# WheelLED_Light_Sch.net
KiCad netlist of a schematic drawn in Altium Designer
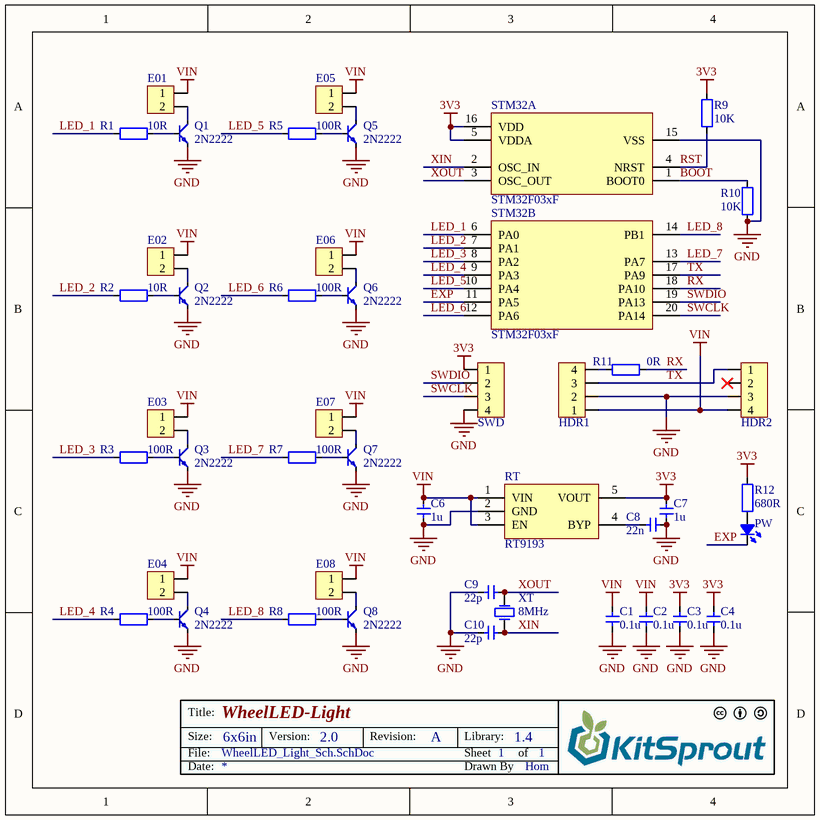
[diagram p0: WheelLED_Light_Sch.SchDoc]

(export (version "E")
  (design (tool "Eeschema 10.0.6"))
  (components
    (comp (ref "C1")
      (value "0.1u")
      (footprint "PCB_PassiveCap:CAP_0603")
      (description "Capacitor")
      (fields (field (name "Comment") "Cap_0603"))
      (libsource (lib "SCH_Passive") (part "Cap_0603"))
    )
    (comp (ref "C2")
      (value "0.1u")
      (footprint "PCB_PassiveCap:CAP_0603")
      (description "Capacitor")
      (fields (field (name "Comment") "Cap_0603"))
      (libsource (lib "SCH_Passive") (part "Cap_0603"))
    )
    (comp (ref "C3")
      (value "0.1u")
      (footprint "PCB_PassiveCap:CAP_0603")
      (description "Capacitor")
      (fields (field (name "Comment") "Cap_0603"))
      (libsource (lib "SCH_Passive") (part "Cap_0603"))
    )
    (comp (ref "C4")
      (value "0.1u")
      (footprint "PCB_PassiveCap:CAP_0603")
      (description "Capacitor")
      (fields (field (name "Comment") "Cap_0603"))
      (libsource (lib "SCH_Passive") (part "Cap_0603"))
    )
    (comp (ref "C6")
      (value "1u")
      (footprint "PCB_PassiveCap:CAP_0603")
      (description "Capacitor")
      (fields (field (name "Comment") "Cap_0603"))
      (libsource (lib "SCH_Passive") (part "Cap_0603"))
    )
    (comp (ref "C7")
      (value "1u")
      (footprint "PCB_PassiveCap:CAP_0603")
      (description "Capacitor")
      (fields (field (name "Comment") "Cap_0603"))
      (libsource (lib "SCH_Passive") (part "Cap_0603"))
    )
    (comp (ref "C8")
      (value "22n")
      (footprint "PCB_PassiveCap:CAP_0603")
      (description "Capacitor")
      (fields (field (name "Comment") "Cap_0603"))
      (libsource (lib "SCH_Passive") (part "Cap_0603"))
    )
    (comp (ref "C9")
      (value "22p")
      (footprint "PCB_PassiveCap:CAP_0603")
      (description "Capacitor")
      (fields (field (name "Comment") "Cap_0603"))
      (libsource (lib "SCH_Passive") (part "Cap_0603"))
    )
    (comp (ref "C10")
      (value "22p")
      (footprint "PCB_PassiveCap:CAP_0603")
      (description "Capacitor")
      (fields (field (name "Comment") "Cap_0603"))
      (libsource (lib "SCH_Passive") (part "Cap_0603"))
    )
    (comp (ref "E01")
      (value "HDR1x2_2.54")
      (footprint "PCB_ConnectorHDR:HDR1X2_2.54_180H")
      (description "Header")
      (libsource (lib "SCH_ConnectorHDR") (part "HDR1x2_2.54T"))
    )
    (comp (ref "E02")
      (value "HDR1x2_2.54")
      (footprint "PCB_ConnectorHDR:HDR1X2_2.54_180H")
      (description "Header")
      (libsource (lib "SCH_ConnectorHDR") (part "HDR1x2_2.54T"))
    )
    (comp (ref "E03")
      (value "HDR1x2_2.54")
      (footprint "PCB_ConnectorHDR:HDR1X2_2.54_180H")
      (description "Header")
      (libsource (lib "SCH_ConnectorHDR") (part "HDR1x2_2.54T"))
    )
    (comp (ref "E04")
      (value "HDR1x2_2.54")
      (footprint "PCB_ConnectorHDR:HDR1X2_2.54_180H")
      (description "Header")
      (libsource (lib "SCH_ConnectorHDR") (part "HDR1x2_2.54T"))
    )
    (comp (ref "E05")
      (value "HDR1x2_2.54")
      (footprint "PCB_ConnectorHDR:HDR1X2_2.54_180H")
      (description "Header")
      (libsource (lib "SCH_ConnectorHDR") (part "HDR1x2_2.54T"))
    )
    (comp (ref "E06")
      (value "HDR1x2_2.54")
      (footprint "PCB_ConnectorHDR:HDR1X2_2.54_180H")
      (description "Header")
      (libsource (lib "SCH_ConnectorHDR") (part "HDR1x2_2.54T"))
    )
    (comp (ref "E07")
      (value "HDR1x2_2.54")
      (footprint "PCB_ConnectorHDR:HDR1X2_2.54_180H")
      (description "Header")
      (libsource (lib "SCH_ConnectorHDR") (part "HDR1x2_2.54T"))
    )
    (comp (ref "E08")
      (value "HDR1x2_2.54")
      (footprint "PCB_ConnectorHDR:HDR1X2_2.54_180H")
      (description "Header")
      (libsource (lib "SCH_ConnectorHDR") (part "HDR1x2_2.54T"))
    )
    (comp (ref "HDR1")
      (value "HDR1x4_2.54")
      (footprint "PCB_ConnectorHDR:HDR1X4_2.54_90F")
      (description "Header")
      (libsource (lib "SCH_ConnectorHDR") (part "HDR1x4_2.54"))
    )
    (comp (ref "HDR2")
      (value "HDR1x4_2.54")
      (footprint "PCB_ConnectorHDR:HDR1X4_2.54_180H")
      (description "Header")
      (libsource (lib "") (part "HDR1x4_2.54_1"))
    )
    (comp (ref "PW")
      (value "LED_0805")
      (footprint "PCB_ActiveLED:LED_0805_GREEN")
      (description "LED")
      (libsource (lib "SCH_Active") (part "LED_0805"))
    )
    (comp (ref "Q1")
      (value "2N2222")
      (footprint "PCB_IntegratedCircuit:SOT23-3")
      (description "Transistor")
      (fields (field (name "Comment") "BJT_NPN"))
      (libsource (lib "SCH_Active") (part "BJT_NPN"))
    )
    (comp (ref "Q2")
      (value "2N2222")
      (footprint "PCB_IntegratedCircuit:SOT23-3")
      (description "Transistor")
      (fields (field (name "Comment") "BJT_NPN"))
      (libsource (lib "SCH_Active") (part "BJT_NPN"))
    )
    (comp (ref "Q3")
      (value "2N2222")
      (footprint "PCB_IntegratedCircuit:SOT23-3")
      (description "Transistor")
      (fields (field (name "Comment") "BJT_NPN"))
      (libsource (lib "SCH_Active") (part "BJT_NPN"))
    )
    (comp (ref "Q4")
      (value "2N2222")
      (footprint "PCB_IntegratedCircuit:SOT23-3")
      (description "Transistor")
      (fields (field (name "Comment") "BJT_NPN"))
      (libsource (lib "SCH_Active") (part "BJT_NPN"))
    )
    (comp (ref "Q5")
      (value "2N2222")
      (footprint "PCB_IntegratedCircuit:SOT23-3")
      (description "Transistor")
      (fields (field (name "Comment") "BJT_NPN"))
      (libsource (lib "SCH_Active") (part "BJT_NPN"))
    )
    (comp (ref "Q6")
      (value "2N2222")
      (footprint "PCB_IntegratedCircuit:SOT23-3")
      (description "Transistor")
      (fields (field (name "Comment") "BJT_NPN"))
      (libsource (lib "SCH_Active") (part "BJT_NPN"))
    )
    (comp (ref "Q7")
      (value "2N2222")
      (footprint "PCB_IntegratedCircuit:SOT23-3")
      (description "Transistor")
      (fields (field (name "Comment") "BJT_NPN"))
      (libsource (lib "SCH_Active") (part "BJT_NPN"))
    )
    (comp (ref "Q8")
      (value "2N2222")
      (footprint "PCB_IntegratedCircuit:SOT23-3")
      (description "Transistor")
      (fields (field (name "Comment") "BJT_NPN"))
      (libsource (lib "SCH_Active") (part "BJT_NPN"))
    )
    (comp (ref "R1")
      (value "10R")
      (footprint "PCB_PassiveRes:RES_0603")
      (description "Resistor")
      (fields (field (name "Comment") "Res_0603"))
      (libsource (lib "SCH_Passive") (part "Res_0603"))
    )
    (comp (ref "R2")
      (value "10R")
      (footprint "PCB_PassiveRes:RES_0603")
      (description "Resistor")
      (fields (field (name "Comment") "Res_0603"))
      (libsource (lib "SCH_Passive") (part "Res_0603"))
    )
    (comp (ref "R3")
      (value "100R")
      (footprint "PCB_PassiveRes:RES_0603")
      (description "Resistor")
      (fields (field (name "Comment") "Res_0603"))
      (libsource (lib "SCH_Passive") (part "Res_0603"))
    )
    (comp (ref "R4")
      (value "100R")
      (footprint "PCB_PassiveRes:RES_0603")
      (description "Resistor")
      (fields (field (name "Comment") "Res_0603"))
      (libsource (lib "SCH_Passive") (part "Res_0603"))
    )
    (comp (ref "R5")
      (value "100R")
      (footprint "PCB_PassiveRes:RES_0603")
      (description "Resistor")
      (fields (field (name "Comment") "Res_0603"))
      (libsource (lib "SCH_Passive") (part "Res_0603"))
    )
    (comp (ref "R6")
      (value "100R")
      (footprint "PCB_PassiveRes:RES_0603")
      (description "Resistor")
      (fields (field (name "Comment") "Res_0603"))
      (libsource (lib "SCH_Passive") (part "Res_0603"))
    )
    (comp (ref "R7")
      (value "100R")
      (footprint "PCB_PassiveRes:RES_0603")
      (description "Resistor")
      (fields (field (name "Comment") "Res_0603"))
      (libsource (lib "SCH_Passive") (part "Res_0603"))
    )
    (comp (ref "R8")
      (value "100R")
      (footprint "PCB_PassiveRes:RES_0603")
      (description "Resistor")
      (fields (field (name "Comment") "Res_0603"))
      (libsource (lib "SCH_Passive") (part "Res_0603"))
    )
    (comp (ref "R9")
      (value "10K")
      (footprint "PCB_PassiveRes:RES_0603")
      (description "Resistor")
      (fields (field (name "Comment") "Res_0603"))
      (libsource (lib "") (part "Res_0603_1"))
    )
    (comp (ref "R10")
      (value "10K")
      (footprint "PCB_PassiveRes:RES_0603")
      (description "Resistor")
      (fields (field (name "Comment") "Res_0603"))
      (libsource (lib "") (part "Res_0603_1"))
    )
    (comp (ref "R11")
      (value "0R")
      (footprint "PCB_PassiveRes:RES_0603")
      (description "Resistor")
      (fields (field (name "Comment") "Res_0603"))
      (libsource (lib "SCH_Passive") (part "Res_0603"))
    )
    (comp (ref "R12")
      (value "680R")
      (footprint "PCB_PassiveRes:RES_0805")
      (description "Resistor")
      (fields (field (name "Comment") "Res_0805"))
      (libsource (lib "SCH_Passive") (part "Res_0805"))
    )
    (comp (ref "RT")
      (value "RT9193")
      (footprint "PCB_IntegratedCircuit:SOT23-5")
      (description "Power")
      (libsource (lib "SCH_IntegratedCircuit") (part "RT9193"))
    )
    (comp (ref "STM32")
      (value "STM32F03xF")
      (footprint "PCB_IntegratedCircuit:TSSOP_E170_P0.65_20")
      (description "MCU")
      (libsource (lib "SCH_IntegratedCircuit") (part "STM32F03xF"))
    )
    (comp (ref "SWD")
      (value "HDR1x4_1.27")
      (footprint "PCB_ConnectorHDR:HDR1X4_1.27_180")
      (description "Header")
      (libsource (lib "SCH_ConnectorHDR") (part "HDR1x4_1.27"))
    )
    (comp (ref "XT")
      (value "8MHz")
      (footprint "PCB_Oscillator:XT_3225_2")
      (description "Crystal Oscillator")
      (fields (field (name "Comment") "XTAL_3225_2P"))
      (libsource (lib "SCH_Oscillator") (part "XTAL_3225_2P"))
    )
  )
  (nets
    (net (code "1") (name "/BOOT") (class "Default")
      (node (ref "R10") (pin "1") (pinfunction "1_1") (pintype "passive"))
      (node (ref "STM32") (pin "1") (pinfunction "BOOT0_1") (pintype "passive"))
    )
    (net (code "2") (name "/EXP") (class "Default")
      (node (ref "PW") (pin "2") (pinfunction "K_2") (pintype "passive"))
      (node (ref "STM32") (pin "11") (pinfunction "PA5_11") (pintype "passive"))
    )
    (net (code "3") (name "/LED_1") (class "Default")
      (node (ref "R1") (pin "1") (pinfunction "1_1") (pintype "passive"))
      (node (ref "STM32") (pin "6") (pinfunction "PA0_6") (pintype "passive"))
    )
    (net (code "4") (name "/LED_2") (class "Default")
      (node (ref "R2") (pin "1") (pinfunction "1_1") (pintype "passive"))
      (node (ref "STM32") (pin "7") (pinfunction "PA1_7") (pintype "passive"))
    )
    (net (code "5") (name "/LED_3") (class "Default")
      (node (ref "R3") (pin "1") (pinfunction "1_1") (pintype "passive"))
      (node (ref "STM32") (pin "8") (pinfunction "PA2_8") (pintype "passive"))
    )
    (net (code "6") (name "/LED_4") (class "Default")
      (node (ref "R4") (pin "1") (pinfunction "1_1") (pintype "passive"))
      (node (ref "STM32") (pin "9") (pinfunction "PA3_9") (pintype "passive"))
    )
    (net (code "7") (name "/LED_5") (class "Default")
      (node (ref "R5") (pin "1") (pinfunction "1_1") (pintype "passive"))
      (node (ref "STM32") (pin "10") (pinfunction "PA4_10") (pintype "passive"))
    )
    (net (code "8") (name "/LED_6") (class "Default")
      (node (ref "R6") (pin "1") (pinfunction "1_1") (pintype "passive"))
      (node (ref "STM32") (pin "12") (pinfunction "PA6_12") (pintype "passive"))
    )
    (net (code "9") (name "/LED_7") (class "Default")
      (node (ref "R7") (pin "1") (pinfunction "1_1") (pintype "passive"))
      (node (ref "STM32") (pin "13") (pinfunction "PA7_13") (pintype "passive"))
    )
    (net (code "10") (name "/LED_8") (class "Default")
      (node (ref "R8") (pin "1") (pinfunction "1_1") (pintype "passive"))
      (node (ref "STM32") (pin "14") (pinfunction "PB1_14") (pintype "passive"))
    )
    (net (code "11") (name "/RST") (class "Default")
      (node (ref "R9") (pin "2") (pinfunction "2_2") (pintype "passive"))
      (node (ref "STM32") (pin "4") (pinfunction "NRST_4") (pintype "passive"))
    )
    (net (code "12") (name "/RX") (class "Default")
      (node (ref "R11") (pin "2") (pinfunction "2_2") (pintype "passive"))
      (node (ref "STM32") (pin "18") (pinfunction "PA10_18") (pintype "passive"))
    )
    (net (code "13") (name "/SWCLK") (class "Default")
      (node (ref "STM32") (pin "20") (pinfunction "PA14_20") (pintype "passive"))
      (node (ref "SWD") (pin "3") (pinfunction "3_3") (pintype "passive"))
    )
    (net (code "14") (name "/SWDIO") (class "Default")
      (node (ref "STM32") (pin "19") (pinfunction "PA13_19") (pintype "passive"))
      (node (ref "SWD") (pin "2") (pinfunction "2_2") (pintype "passive"))
    )
    (net (code "15") (name "/TX") (class "Default")
      (node (ref "HDR1") (pin "3") (pinfunction "3_3") (pintype "passive"))
      (node (ref "HDR2") (pin "1") (pinfunction "1_1") (pintype "passive"))
      (node (ref "STM32") (pin "17") (pinfunction "PA9_17") (pintype "passive"))
    )
    (net (code "16") (name "/XIN") (class "Default")
      (node (ref "C10") (pin "1") (pinfunction "1_1") (pintype "passive"))
      (node (ref "STM32") (pin "2") (pinfunction "OSC_IN_2") (pintype "passive"))
      (node (ref "XT") (pin "1") (pinfunction "OSC1_1") (pintype "passive"))
    )
    (net (code "17") (name "/XOUT") (class "Default")
      (node (ref "C9") (pin "1") (pinfunction "1_1") (pintype "passive"))
      (node (ref "STM32") (pin "3") (pinfunction "OSC_OUT_3") (pintype "passive"))
      (node (ref "XT") (pin "2") (pinfunction "OSC2_2") (pintype "passive"))
    )
    (net (code "18") (name "3V3") (class "Default")
      (node (ref "C3") (pin "2") (pinfunction "2_2") (pintype "passive"))
      (node (ref "C4") (pin "2") (pinfunction "2_2") (pintype "passive"))
      (node (ref "C7") (pin "2") (pinfunction "2_2") (pintype "passive"))
      (node (ref "R12") (pin "2") (pinfunction "2_2") (pintype "passive"))
      (node (ref "R9") (pin "1") (pinfunction "1_1") (pintype "passive"))
      (node (ref "RT") (pin "5") (pinfunction "VOUT_5") (pintype "passive"))
      (node (ref "STM32") (pin "16") (pinfunction "VDD_16") (pintype "passive"))
      (node (ref "STM32") (pin "5") (pinfunction "VDDA_5") (pintype "passive"))
      (node (ref "SWD") (pin "1") (pinfunction "1_1") (pintype "passive"))
    )
    (net (code "19") (name "GND") (class "Default")
      (node (ref "C1") (pin "1") (pinfunction "1_1") (pintype "passive"))
      (node (ref "C10") (pin "2") (pinfunction "2_2") (pintype "passive"))
      (node (ref "C2") (pin "1") (pinfunction "1_1") (pintype "passive"))
      (node (ref "C3") (pin "1") (pinfunction "1_1") (pintype "passive"))
      (node (ref "C4") (pin "1") (pinfunction "1_1") (pintype "passive"))
      (node (ref "C6") (pin "1") (pinfunction "1_1") (pintype "passive"))
      (node (ref "C7") (pin "1") (pinfunction "1_1") (pintype "passive"))
      (node (ref "C8") (pin "1") (pinfunction "1_1") (pintype "passive"))
      (node (ref "C9") (pin "2") (pinfunction "2_2") (pintype "passive"))
      (node (ref "HDR1") (pin "2") (pinfunction "2_2") (pintype "passive"))
      (node (ref "HDR2") (pin "3") (pinfunction "3_3") (pintype "passive"))
      (node (ref "Q1") (pin "2") (pinfunction "E_2") (pintype "passive"))
      (node (ref "Q2") (pin "2") (pinfunction "E_2") (pintype "passive"))
      (node (ref "Q3") (pin "2") (pinfunction "E_2") (pintype "passive"))
      (node (ref "Q4") (pin "2") (pinfunction "E_2") (pintype "passive"))
      (node (ref "Q5") (pin "2") (pinfunction "E_2") (pintype "passive"))
      (node (ref "Q6") (pin "2") (pinfunction "E_2") (pintype "passive"))
      (node (ref "Q7") (pin "2") (pinfunction "E_2") (pintype "passive"))
      (node (ref "Q8") (pin "2") (pinfunction "E_2") (pintype "passive"))
      (node (ref "R10") (pin "2") (pinfunction "2_2") (pintype "passive"))
      (node (ref "RT") (pin "2") (pinfunction "GND_2") (pintype "passive"))
      (node (ref "STM32") (pin "15") (pinfunction "VSS_15") (pintype "passive"))
      (node (ref "SWD") (pin "4") (pinfunction "4_4") (pintype "passive"))
    )
    (net (code "20") (name "Net-(HDR1-Pad4)") (class "Default")
      (node (ref "HDR1") (pin "4") (pinfunction "4_4") (pintype "passive"))
      (node (ref "R11") (pin "1") (pinfunction "1_1") (pintype "passive"))
    )
    (net (code "21") (name "Net-(PW-A)") (class "Default")
      (node (ref "PW") (pin "1") (pinfunction "A_1") (pintype "passive"))
      (node (ref "R12") (pin "1") (pinfunction "1_1") (pintype "passive"))
    )
    (net (code "22") (name "Net-(Q1-B)") (class "Default")
      (node (ref "Q1") (pin "1") (pinfunction "B_1") (pintype "passive"))
      (node (ref "R1") (pin "2") (pinfunction "2_2") (pintype "passive"))
    )
    (net (code "23") (name "Net-(Q1-C)") (class "Default")
      (node (ref "E01") (pin "2") (pinfunction "2_2") (pintype "passive"))
      (node (ref "Q1") (pin "3") (pinfunction "C_3") (pintype "passive"))
    )
    (net (code "24") (name "Net-(Q2-B)") (class "Default")
      (node (ref "Q2") (pin "1") (pinfunction "B_1") (pintype "passive"))
      (node (ref "R2") (pin "2") (pinfunction "2_2") (pintype "passive"))
    )
    (net (code "25") (name "Net-(Q2-C)") (class "Default")
      (node (ref "E02") (pin "2") (pinfunction "2_2") (pintype "passive"))
      (node (ref "Q2") (pin "3") (pinfunction "C_3") (pintype "passive"))
    )
    (net (code "26") (name "Net-(Q3-B)") (class "Default")
      (node (ref "Q3") (pin "1") (pinfunction "B_1") (pintype "passive"))
      (node (ref "R3") (pin "2") (pinfunction "2_2") (pintype "passive"))
    )
    (net (code "27") (name "Net-(Q3-C)") (class "Default")
      (node (ref "E03") (pin "2") (pinfunction "2_2") (pintype "passive"))
      (node (ref "Q3") (pin "3") (pinfunction "C_3") (pintype "passive"))
    )
    (net (code "28") (name "Net-(Q4-B)") (class "Default")
      (node (ref "Q4") (pin "1") (pinfunction "B_1") (pintype "passive"))
      (node (ref "R4") (pin "2") (pinfunction "2_2") (pintype "passive"))
    )
    (net (code "29") (name "Net-(Q4-C)") (class "Default")
      (node (ref "E04") (pin "2") (pinfunction "2_2") (pintype "passive"))
      (node (ref "Q4") (pin "3") (pinfunction "C_3") (pintype "passive"))
    )
    (net (code "30") (name "Net-(Q5-B)") (class "Default")
      (node (ref "Q5") (pin "1") (pinfunction "B_1") (pintype "passive"))
      (node (ref "R5") (pin "2") (pinfunction "2_2") (pintype "passive"))
    )
    (net (code "31") (name "Net-(Q5-C)") (class "Default")
      (node (ref "E05") (pin "2") (pinfunction "2_2") (pintype "passive"))
      (node (ref "Q5") (pin "3") (pinfunction "C_3") (pintype "passive"))
    )
    (net (code "32") (name "Net-(Q6-B)") (class "Default")
      (node (ref "Q6") (pin "1") (pinfunction "B_1") (pintype "passive"))
      (node (ref "R6") (pin "2") (pinfunction "2_2") (pintype "passive"))
    )
    (net (code "33") (name "Net-(Q6-C)") (class "Default")
      (node (ref "E06") (pin "2") (pinfunction "2_2") (pintype "passive"))
      (node (ref "Q6") (pin "3") (pinfunction "C_3") (pintype "passive"))
    )
    (net (code "34") (name "Net-(Q7-B)") (class "Default")
      (node (ref "Q7") (pin "1") (pinfunction "B_1") (pintype "passive"))
      (node (ref "R7") (pin "2") (pinfunction "2_2") (pintype "passive"))
    )
    (net (code "35") (name "Net-(Q7-C)") (class "Default")
      (node (ref "E07") (pin "2") (pinfunction "2_2") (pintype "passive"))
      (node (ref "Q7") (pin "3") (pinfunction "C_3") (pintype "passive"))
    )
    (net (code "36") (name "Net-(Q8-B)") (class "Default")
      (node (ref "Q8") (pin "1") (pinfunction "B_1") (pintype "passive"))
      (node (ref "R8") (pin "2") (pinfunction "2_2") (pintype "passive"))
    )
    (net (code "37") (name "Net-(Q8-C)") (class "Default")
      (node (ref "E08") (pin "2") (pinfunction "2_2") (pintype "passive"))
      (node (ref "Q8") (pin "3") (pinfunction "C_3") (pintype "passive"))
    )
    (net (code "38") (name "Net-(RT-BYP)") (class "Default")
      (node (ref "C8") (pin "2") (pinfunction "2_2") (pintype "passive"))
      (node (ref "RT") (pin "4") (pinfunction "BYP_4") (pintype "passive"))
    )
    (net (code "39") (name "VIN") (class "Default")
      (node (ref "C1") (pin "2") (pinfunction "2_2") (pintype "passive"))
      (node (ref "C2") (pin "2") (pinfunction "2_2") (pintype "passive"))
      (node (ref "C6") (pin "2") (pinfunction "2_2") (pintype "passive"))
      (node (ref "E01") (pin "1") (pinfunction "1_1") (pintype "passive"))
      (node (ref "E02") (pin "1") (pinfunction "1_1") (pintype "passive"))
      (node (ref "E03") (pin "1") (pinfunction "1_1") (pintype "passive"))
      (node (ref "E04") (pin "1") (pinfunction "1_1") (pintype "passive"))
      (node (ref "E05") (pin "1") (pinfunction "1_1") (pintype "passive"))
      (node (ref "E06") (pin "1") (pinfunction "1_1") (pintype "passive"))
      (node (ref "E07") (pin "1") (pinfunction "1_1") (pintype "passive"))
      (node (ref "E08") (pin "1") (pinfunction "1_1") (pintype "passive"))
      (node (ref "HDR1") (pin "1") (pinfunction "1_1") (pintype "passive"))
      (node (ref "HDR2") (pin "4") (pinfunction "4_4") (pintype "passive"))
      (node (ref "RT") (pin "1") (pinfunction "VIN_1") (pintype "passive"))
      (node (ref "RT") (pin "3") (pinfunction "EN_3") (pintype "power_in"))
    )
    (net (code "40") (name "unconnected-(HDR2-Pad2)") (class "Default")
      (node (ref "HDR2") (pin "2") (pinfunction "2_2") (pintype "passive+no_connect"))
    )
  )
)
